# tempLogger_Arduino.net
KiCad netlist of a schematic drawn in EAGLE
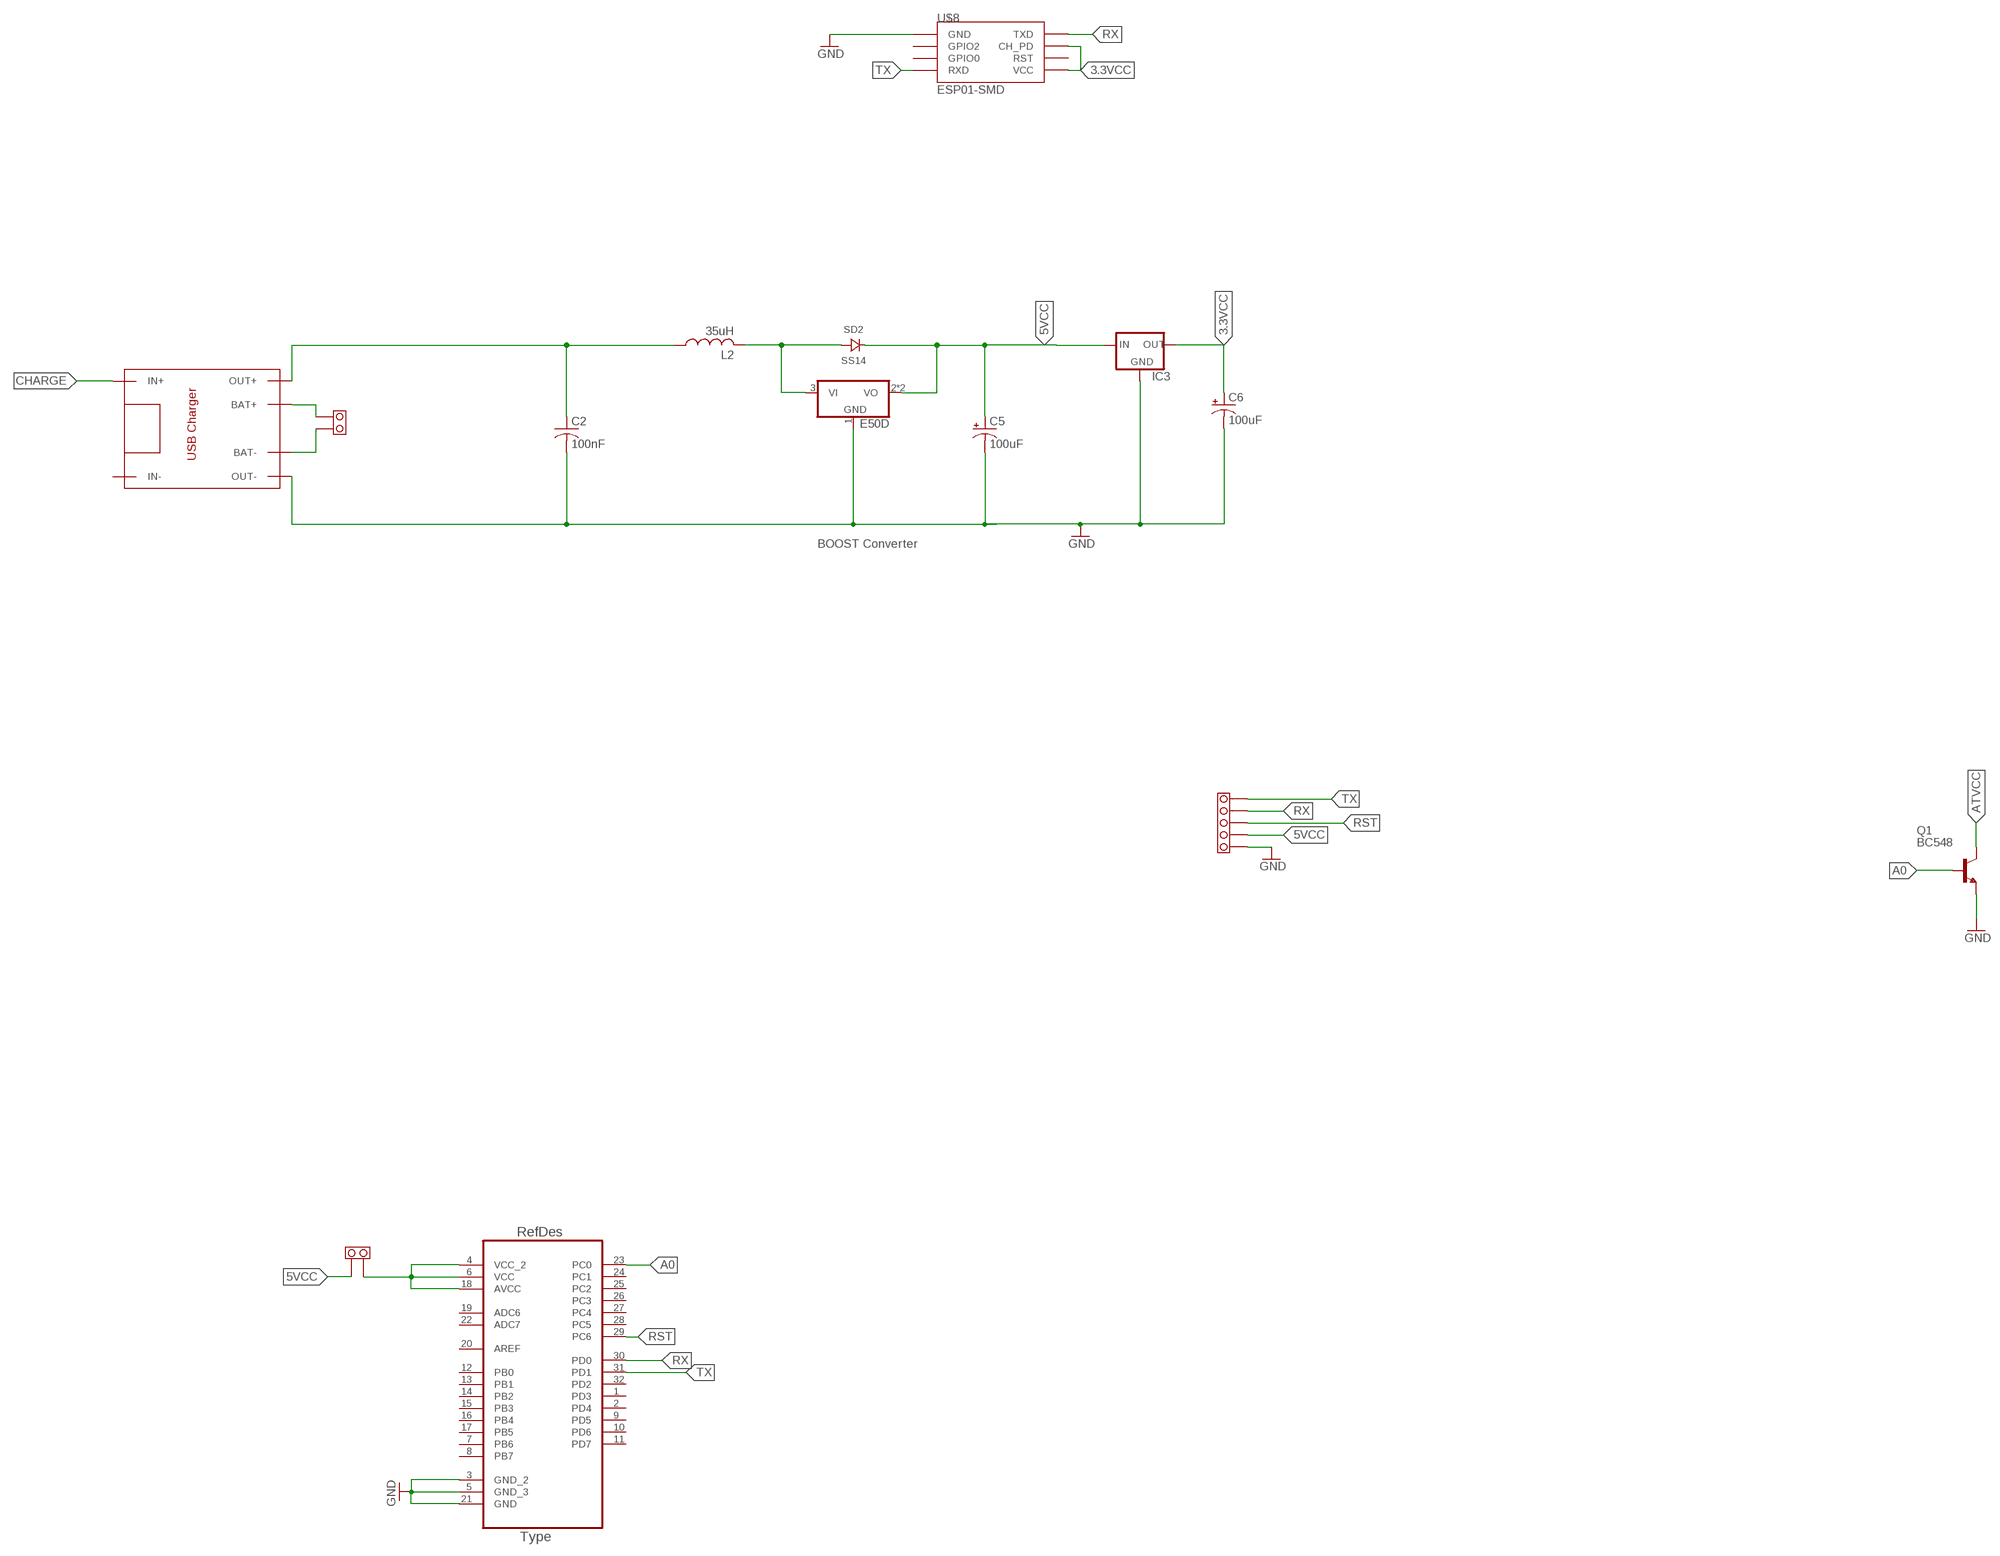
[diagram p0: schematic, sheet 1]

(export (version "E")
  (design (tool "Eeschema 10.0.6"))
  (components
    (comp (ref "C2")
      (value "100nF")
      (footprint "eagle-import:C1206")
      (libsource (lib "eagle-import") (part "C-USC1206"))
    )
    (comp (ref "C5")
      (value "100uF")
      (footprint "eagle-import:150CLZ-0810")
      (libsource (lib "eagle-import") (part "CPOL-US150CLZ-0810"))
    )
    (comp (ref "C6")
      (value "100uF")
      (footprint "eagle-import:153CLV-0405")
      (libsource (lib "eagle-import") (part "CPOL-US153CLV-0405"))
    )
    (comp (ref "IC2")
      (value "E50D")
      (footprint "eagle-import:SOT89")
      (libsource (lib "eagle-import") (part "E50D"))
    )
    (comp (ref "IC3")
      (value "LM1117")
      (footprint "eagle-import:SOT223")
      (libsource (lib "eagle-import") (part "LM1117"))
    )
    (comp (ref "L2")
      (value "35uH")
      (footprint "eagle-import:POWER-CHOKE_WE-TPC")
      (libsource (lib "eagle-import") (part "L-USWE-TPC"))
    )
    (comp (ref "Q1")
      (value "BC548")
      (footprint "eagle-import:TO92-EBC")
      (libsource (lib "eagle-import") (part "BC548"))
    )
    (comp (ref "SD2")
      (value "SS14")
      (footprint "eagle-import:DO214")
      (libsource (lib "eagle-import") (part "SS14"))
    )
    (comp (ref "U$2")
      (value "TP4056")
      (footprint "eagle-import:TP4056")
      (libsource (lib "eagle-import") (part "TP4056"))
    )
    (comp (ref "U$3")
      (value "BERG_5")
      (footprint "eagle-import:BERG_5")
      (libsource (lib "eagle-import") (part "BERG_5"))
    )
    (comp (ref "U$4")
      (value "BERG_2")
      (footprint "eagle-import:BERG_2")
      (libsource (lib "eagle-import") (part "BERG_2"))
    )
    (comp (ref "U$5")
      (value "BERG_2")
      (footprint "eagle-import:BERG_2")
      (libsource (lib "eagle-import") (part "BERG_2"))
    )
    (comp (ref "U$8")
      (value "ESP01-SMD")
      (footprint "eagle-import:ESP01_SMD")
      (libsource (lib "eagle-import") (part "ESP01-SMD"))
    )
    (comp (ref "U1")
      (value "ATMEGA328P-AU")
      (footprint "eagle-import:QFP80P900X900X120-32N")
      (libsource (lib "eagle-import") (part "ATMEGA328P-AU"))
    )
  )
  (nets
    (net (code "1") (name "3.3VCC") (class "Default")
      (node (ref "C6") (pin "+") (pinfunction "+_+") (pintype "passive"))
      (node (ref "IC3") (pin "2") (pinfunction "OUT_2") (pintype "passive"))
      (node (ref "U$8") (pin "CH_PD") (pinfunction "CH_PD_CH_PD") (pintype "bidirectional"))
      (node (ref "U$8") (pin "VCC") (pinfunction "VCC_VCC") (pintype "bidirectional"))
    )
    (net (code "2") (name "5VCC") (class "Default")
      (node (ref "C5") (pin "+") (pinfunction "+_+") (pintype "passive"))
      (node (ref "IC2") (pin "2") (pinfunction "VO_2") (pintype "passive"))
      (node (ref "IC2") (pin "2@1") (pinfunction "VO_2@1") (pintype "passive"))
      (node (ref "IC3") (pin "3") (pinfunction "IN_3") (pintype "input"))
      (node (ref "SD2") (pin "CATHODE") (pinfunction "CATHODE_CATHODE") (pintype "bidirectional"))
      (node (ref "U$3") (pin "H") (pinfunction "P$4_H") (pintype "bidirectional"))
      (node (ref "U$5") (pin "F") (pinfunction "P$2_F") (pintype "bidirectional"))
    )
    (net (code "3") (name "A0") (class "Default")
      (node (ref "Q1") (pin "B") (pinfunction "B_B") (pintype "passive"))
      (node (ref "U1") (pin "23") (pinfunction "PC0_23") (pintype "bidirectional"))
    )
    (net (code "4") (name "ATVCC") (class "Default")
      (node (ref "Q1") (pin "C") (pinfunction "C_C") (pintype "passive"))
      (node (ref "U$5") (pin "E") (pinfunction "P$1_E") (pintype "bidirectional"))
      (node (ref "U1") (pin "18") (pinfunction "AVCC_18") (pintype "power_in"))
      (node (ref "U1") (pin "4") (pinfunction "VCC_2_4") (pintype "power_in"))
      (node (ref "U1") (pin "6") (pinfunction "VCC_6") (pintype "power_in"))
    )
    (net (code "5") (name "CHARGE") (class "Default")
      (node (ref "U$2") (pin "IN+") (pinfunction "IN+_IN+") (pintype "bidirectional"))
    )
    (net (code "6") (name "GND") (class "Default")
      (node (ref "C2") (pin "2") (pinfunction "2_2") (pintype "passive"))
      (node (ref "C5") (pin "-") (pinfunction "-_-") (pintype "passive"))
      (node (ref "C6") (pin "-") (pinfunction "-_-") (pintype "passive"))
      (node (ref "IC2") (pin "1") (pinfunction "GND_1") (pintype "passive"))
      (node (ref "IC3") (pin "1") (pinfunction "GND_1") (pintype "input"))
      (node (ref "Q1") (pin "E") (pinfunction "E_E") (pintype "passive"))
      (node (ref "U$2") (pin "OUT-") (pinfunction "OUT-_OUT-") (pintype "bidirectional"))
      (node (ref "U$3") (pin "I") (pinfunction "P$5_I") (pintype "bidirectional"))
      (node (ref "U$8") (pin "GND") (pinfunction "GND_GND") (pintype "bidirectional"))
      (node (ref "U1") (pin "21") (pinfunction "GND_21") (pintype "passive"))
      (node (ref "U1") (pin "3") (pinfunction "GND_2_3") (pintype "passive"))
      (node (ref "U1") (pin "5") (pinfunction "GND_3_5") (pintype "passive"))
    )
    (net (code "7") (name "Net-(C2-Pad1)") (class "Default")
      (node (ref "C2") (pin "1") (pinfunction "1_1") (pintype "passive"))
      (node (ref "L2") (pin "1") (pinfunction "1_1") (pintype "passive"))
      (node (ref "U$2") (pin "OUT+") (pinfunction "OUT+_OUT+") (pintype "bidirectional"))
    )
    (net (code "8") (name "Net-(IC2-VI)") (class "Default")
      (node (ref "IC2") (pin "3") (pinfunction "VI_3") (pintype "input"))
      (node (ref "L2") (pin "2") (pinfunction "2_2") (pintype "passive"))
      (node (ref "SD2") (pin "ANODE") (pinfunction "ANODE_ANODE") (pintype "bidirectional"))
    )
    (net (code "9") (name "Net-(U$4-P$1)") (class "Default")
      (node (ref "U$2") (pin "BAT-") (pinfunction "BAT-_BAT-") (pintype "bidirectional"))
      (node (ref "U$4") (pin "E") (pinfunction "P$1_E") (pintype "bidirectional"))
    )
    (net (code "10") (name "Net-(U$4-P$2)") (class "Default")
      (node (ref "U$2") (pin "BAT+") (pinfunction "BAT+_BAT+") (pintype "bidirectional"))
      (node (ref "U$4") (pin "F") (pinfunction "P$2_F") (pintype "bidirectional"))
    )
    (net (code "11") (name "RST") (class "Default")
      (node (ref "U$3") (pin "G") (pinfunction "P$3_G") (pintype "bidirectional"))
      (node (ref "U1") (pin "29") (pinfunction "PC6_29") (pintype "bidirectional"))
    )
    (net (code "12") (name "RX") (class "Default")
      (node (ref "U$3") (pin "F") (pinfunction "P$2_F") (pintype "bidirectional"))
      (node (ref "U$8") (pin "TX") (pinfunction "TXD_TX") (pintype "bidirectional"))
      (node (ref "U1") (pin "30") (pinfunction "PD0_30") (pintype "bidirectional"))
    )
    (net (code "13") (name "TX") (class "Default")
      (node (ref "U$3") (pin "E") (pinfunction "P$1_E") (pintype "bidirectional"))
      (node (ref "U$8") (pin "RX") (pinfunction "RXD_RX") (pintype "bidirectional"))
      (node (ref "U1") (pin "31") (pinfunction "PD1_31") (pintype "bidirectional"))
    )
    (net (code "14") (name "unconnected-(U$2-PadIN-)") (class "Default")
      (node (ref "U$2") (pin "IN-") (pinfunction "IN-_IN-") (pintype "bidirectional"))
    )
    (net (code "15") (name "unconnected-(U$8-PadGPIO0)") (class "Default")
      (node (ref "U$8") (pin "GPIO0") (pinfunction "GPIO0_GPIO0") (pintype "bidirectional"))
    )
    (net (code "16") (name "unconnected-(U$8-PadGPIO2)") (class "Default")
      (node (ref "U$8") (pin "GPIO2") (pinfunction "GPIO2_GPIO2") (pintype "bidirectional"))
    )
    (net (code "17") (name "unconnected-(U$8-PadRST)") (class "Default")
      (node (ref "U$8") (pin "RST") (pinfunction "RST_RST") (pintype "bidirectional"))
    )
    (net (code "18") (name "unconnected-(U1-ADC6-Pad19)") (class "Default")
      (node (ref "U1") (pin "19") (pinfunction "ADC6_19") (pintype "input"))
    )
    (net (code "19") (name "unconnected-(U1-ADC7-Pad22)") (class "Default")
      (node (ref "U1") (pin "22") (pinfunction "ADC7_22") (pintype "input"))
    )
    (net (code "20") (name "unconnected-(U1-AREF-Pad20)") (class "Default")
      (node (ref "U1") (pin "20") (pinfunction "AREF_20") (pintype "input"))
    )
    (net (code "21") (name "unconnected-(U1-PB0-Pad12)") (class "Default")
      (node (ref "U1") (pin "12") (pinfunction "PB0_12") (pintype "bidirectional"))
    )
    (net (code "22") (name "unconnected-(U1-PB1-Pad13)") (class "Default")
      (node (ref "U1") (pin "13") (pinfunction "PB1_13") (pintype "bidirectional"))
    )
    (net (code "23") (name "unconnected-(U1-PB2-Pad14)") (class "Default")
      (node (ref "U1") (pin "14") (pinfunction "PB2_14") (pintype "bidirectional"))
    )
    (net (code "24") (name "unconnected-(U1-PB3-Pad15)") (class "Default")
      (node (ref "U1") (pin "15") (pinfunction "PB3_15") (pintype "bidirectional"))
    )
    (net (code "25") (name "unconnected-(U1-PB4-Pad16)") (class "Default")
      (node (ref "U1") (pin "16") (pinfunction "PB4_16") (pintype "bidirectional"))
    )
    (net (code "26") (name "unconnected-(U1-PB5-Pad17)") (class "Default")
      (node (ref "U1") (pin "17") (pinfunction "PB5_17") (pintype "bidirectional"))
    )
    (net (code "27") (name "unconnected-(U1-PB6-Pad7)") (class "Default")
      (node (ref "U1") (pin "7") (pinfunction "PB6_7") (pintype "bidirectional"))
    )
    (net (code "28") (name "unconnected-(U1-PB7-Pad8)") (class "Default")
      (node (ref "U1") (pin "8") (pinfunction "PB7_8") (pintype "bidirectional"))
    )
    (net (code "29") (name "unconnected-(U1-PC1-Pad24)") (class "Default")
      (node (ref "U1") (pin "24") (pinfunction "PC1_24") (pintype "bidirectional"))
    )
    (net (code "30") (name "unconnected-(U1-PC2-Pad25)") (class "Default")
      (node (ref "U1") (pin "25") (pinfunction "PC2_25") (pintype "bidirectional"))
    )
    (net (code "31") (name "unconnected-(U1-PC3-Pad26)") (class "Default")
      (node (ref "U1") (pin "26") (pinfunction "PC3_26") (pintype "bidirectional"))
    )
    (net (code "32") (name "unconnected-(U1-PC4-Pad27)") (class "Default")
      (node (ref "U1") (pin "27") (pinfunction "PC4_27") (pintype "bidirectional"))
    )
    (net (code "33") (name "unconnected-(U1-PC5-Pad28)") (class "Default")
      (node (ref "U1") (pin "28") (pinfunction "PC5_28") (pintype "bidirectional"))
    )
    (net (code "34") (name "unconnected-(U1-PD2-Pad32)") (class "Default")
      (node (ref "U1") (pin "32") (pinfunction "PD2_32") (pintype "bidirectional"))
    )
    (net (code "35") (name "unconnected-(U1-PD3-Pad1)") (class "Default")
      (node (ref "U1") (pin "1") (pinfunction "PD3_1") (pintype "bidirectional"))
    )
    (net (code "36") (name "unconnected-(U1-PD4-Pad2)") (class "Default")
      (node (ref "U1") (pin "2") (pinfunction "PD4_2") (pintype "bidirectional"))
    )
    (net (code "37") (name "unconnected-(U1-PD5-Pad9)") (class "Default")
      (node (ref "U1") (pin "9") (pinfunction "PD5_9") (pintype "bidirectional"))
    )
    (net (code "38") (name "unconnected-(U1-PD6-Pad10)") (class "Default")
      (node (ref "U1") (pin "10") (pinfunction "PD6_10") (pintype "bidirectional"))
    )
    (net (code "39") (name "unconnected-(U1-PD7-Pad11)") (class "Default")
      (node (ref "U1") (pin "11") (pinfunction "PD7_11") (pintype "bidirectional"))
    )
  )
)
